# Lipo-Charger-5V-setup.net
KiCad netlist of a schematic drawn in EAGLE
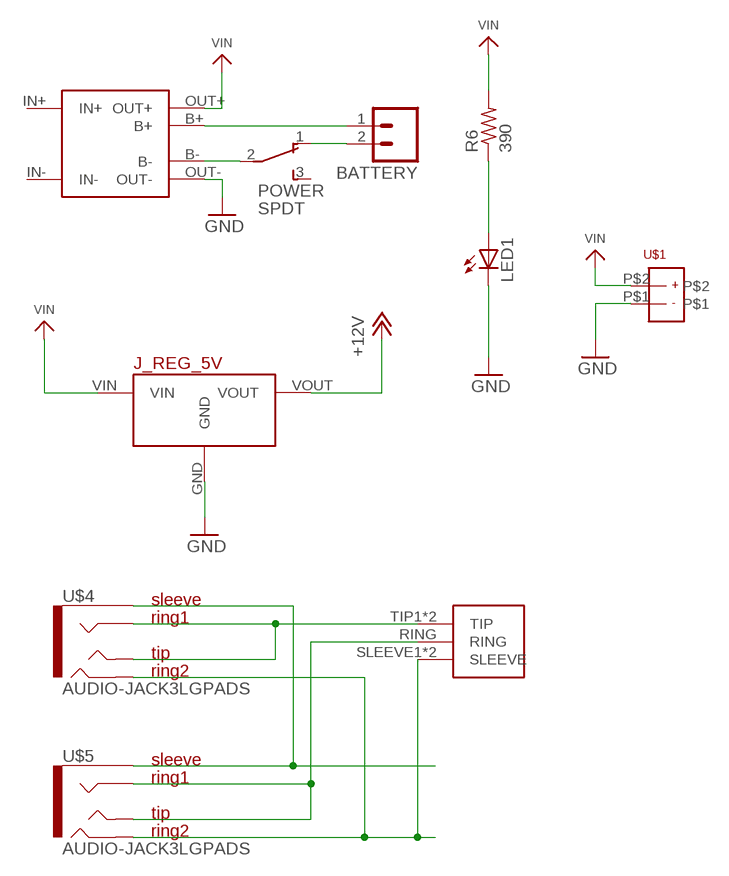
[diagram p0: schematic, sheet 1]

(export (version "E")
  (design (tool "Eeschema 10.0.6"))
  (components
    (comp (ref "AUDIO_OUT")
      (value "1/8\"-F-STEREO-PCB")
      (footprint "eagle-import:1_8_-F-STEREO-PCB")
      (libsource (lib "eagle-import") (part "1/8{dblquote}-F-STEREO-PCB"))
    )
    (comp (ref "BATTERY")
      (value "M02LOCK")
      (footprint "eagle-import:1X02_LOCK")
      (libsource (lib "eagle-import") (part "M02LOCK"))
    )
    (comp (ref "J_REG_5V")
      (value "POLOLU_VOLTAGE_REGULATORS_3PIN")
      (footprint "eagle-import:POLOLU_5V-12V_STEPUP_U3V12F5-U3V12F12")
      (libsource (lib "eagle-import") (part "POLOLU_VOLTAGE_REGULATORS_3PIN"))
    )
    (comp (ref "LED1")
      (value "LED3MM")
      (footprint "eagle-import:LED3MM")
      (libsource (lib "eagle-import") (part "LED3MM"))
    )
    (comp (ref "POWER")
      (value "SPDT")
      (footprint "eagle-import:SWITCH_SPDT-TE-CONNECT")
      (libsource (lib "eagle-import") (part "SWITCH_SPDTTE-CONNECT"))
    )
    (comp (ref "R6")
      (value "390")
      (footprint "eagle-import:0204_7")
      (libsource (lib "eagle-import") (part "R-US_0204/7"))
    )
    (comp (ref "U$1")
      (value "BATTERY-3.7V-1S-LIPOBATTERY_MORPILOT-3.7-1S-720MAH")
      (footprint "eagle-import:BATTERY_MORPILOT-3.7-1S-720MAH")
      (libsource (lib "eagle-import") (part "BATTERY-3.7V-1S-LIPOBATTERY_MORPILOT-3.7-1S-720MAH"))
    )
    (comp (ref "U$4")
      (value "AUDIO-JACK3LGPADS")
      (footprint "eagle-import:AUDIO-JACK-TRRS-SMD")
      (libsource (lib "eagle-import") (part "AUDIO-JACK3LGPADS"))
    )
    (comp (ref "U$5")
      (value "AUDIO-JACK3LGPADS")
      (footprint "eagle-import:AUDIO-JACK-TRRS-SMD")
      (libsource (lib "eagle-import") (part "AUDIO-JACK3LGPADS"))
    )
    (comp (ref "USB-LIPO-CHARGER")
      (value "TP4056-MODULE")
      (footprint "eagle-import:TP4056-LITHIUM-PROTECTED-MODULE")
      (libsource (lib "eagle-import") (part "TP4056-MODULE"))
    )
  )
  (nets
    (net (code "1") (name "+12V") (class "Default")
      (node (ref "J_REG_5V") (pin "VOUT") (pinfunction "VOUT_VOUT") (pintype "bidirectional"))
    )
    (net (code "2") (name "/IN+") (class "Default")
      (node (ref "USB-LIPO-CHARGER") (pin "IN+") (pinfunction "IN+_IN+") (pintype "power_in"))
    )
    (net (code "3") (name "/IN-") (class "Default")
      (node (ref "USB-LIPO-CHARGER") (pin "IN-") (pinfunction "IN-_IN-") (pintype "power_in"))
    )
    (net (code "4") (name "GND") (class "Default")
      (node (ref "J_REG_5V") (pin "GND") (pinfunction "GND_GND") (pintype "bidirectional"))
      (node (ref "LED1") (pin "K") (pinfunction "C_K") (pintype "passive"))
      (node (ref "U$1") (pin "P$1") (pinfunction "P$1_P$1") (pintype "bidirectional"))
      (node (ref "USB-LIPO-CHARGER") (pin "OUT-") (pinfunction "OUT-_OUT-") (pintype "power_in"))
    )
    (net (code "5") (name "Net-(AUDIO_OUT-PadRING)") (class "Default")
      (node (ref "AUDIO_OUT") (pin "RING") (pinfunction "RING_RING") (pintype "bidirectional"))
      (node (ref "U$5") (pin "RING1") (pinfunction "RING1_RING1") (pintype "bidirectional"))
      (node (ref "U$5") (pin "TIP") (pinfunction "TIP_TIP") (pintype "bidirectional"))
    )
    (net (code "6") (name "Net-(AUDIO_OUT-SLEEVE-PadSLEEVE1)") (class "Default")
      (node (ref "AUDIO_OUT") (pin "SLEEVE1") (pinfunction "SLEEVE_SLEEVE1") (pintype "bidirectional"))
      (node (ref "AUDIO_OUT") (pin "SLEEVE2") (pinfunction "SLEEVE_SLEEVE2") (pintype "bidirectional"))
      (node (ref "U$4") (pin "RING2") (pinfunction "RING2_RING2") (pintype "bidirectional"))
      (node (ref "U$5") (pin "RING2") (pinfunction "RING2_RING2") (pintype "bidirectional"))
    )
    (net (code "7") (name "Net-(AUDIO_OUT-TIP-PadTIP1)") (class "Default")
      (node (ref "AUDIO_OUT") (pin "TIP1") (pinfunction "TIP_TIP1") (pintype "bidirectional"))
      (node (ref "AUDIO_OUT") (pin "TIP2") (pinfunction "TIP_TIP2") (pintype "bidirectional"))
      (node (ref "U$4") (pin "RING1") (pinfunction "RING1_RING1") (pintype "bidirectional"))
      (node (ref "U$4") (pin "TIP") (pinfunction "TIP_TIP") (pintype "bidirectional"))
    )
    (net (code "8") (name "Net-(BATTERY-Pad1)") (class "Default")
      (node (ref "BATTERY") (pin "1") (pinfunction "1_1") (pintype "passive"))
      (node (ref "USB-LIPO-CHARGER") (pin "B+") (pinfunction "B+_B+") (pintype "power_in"))
    )
    (net (code "9") (name "Net-(BATTERY-Pad2)") (class "Default")
      (node (ref "BATTERY") (pin "2") (pinfunction "2_2") (pintype "passive"))
      (node (ref "POWER") (pin "1") (pinfunction "1_1") (pintype "passive"))
    )
    (net (code "10") (name "Net-(LED1-PadA)") (class "Default")
      (node (ref "LED1") (pin "A") (pinfunction "A_A") (pintype "passive"))
      (node (ref "R6") (pin "1") (pinfunction "1_1") (pintype "passive"))
    )
    (net (code "11") (name "Net-(POWER-Pad2)") (class "Default")
      (node (ref "POWER") (pin "2") (pinfunction "2_2") (pintype "passive"))
      (node (ref "USB-LIPO-CHARGER") (pin "B-") (pinfunction "B-_B-") (pintype "power_in"))
    )
    (net (code "12") (name "Net-(U$4-PadEARTH)") (class "Default")
      (node (ref "U$4") (pin "EARTH") (pinfunction "EARTH_EARTH") (pintype "bidirectional"))
      (node (ref "U$5") (pin "EARTH") (pinfunction "EARTH_EARTH") (pintype "bidirectional"))
    )
    (net (code "13") (name "VIN") (class "Default")
      (node (ref "J_REG_5V") (pin "VIN") (pinfunction "VIN_VIN") (pintype "bidirectional"))
      (node (ref "R6") (pin "2") (pinfunction "2_2") (pintype "passive"))
      (node (ref "U$1") (pin "P$2") (pinfunction "P$2_P$2") (pintype "bidirectional"))
      (node (ref "USB-LIPO-CHARGER") (pin "OUT+") (pinfunction "OUT+_OUT+") (pintype "power_in"))
    )
    (net (code "14") (name "unconnected-(POWER-Pad3)") (class "Default")
      (node (ref "POWER") (pin "3") (pinfunction "3_3") (pintype "passive"))
    )
  )
)
